# Hive_Server_-_Electron.net
KiCad netlist of a schematic drawn in EAGLE
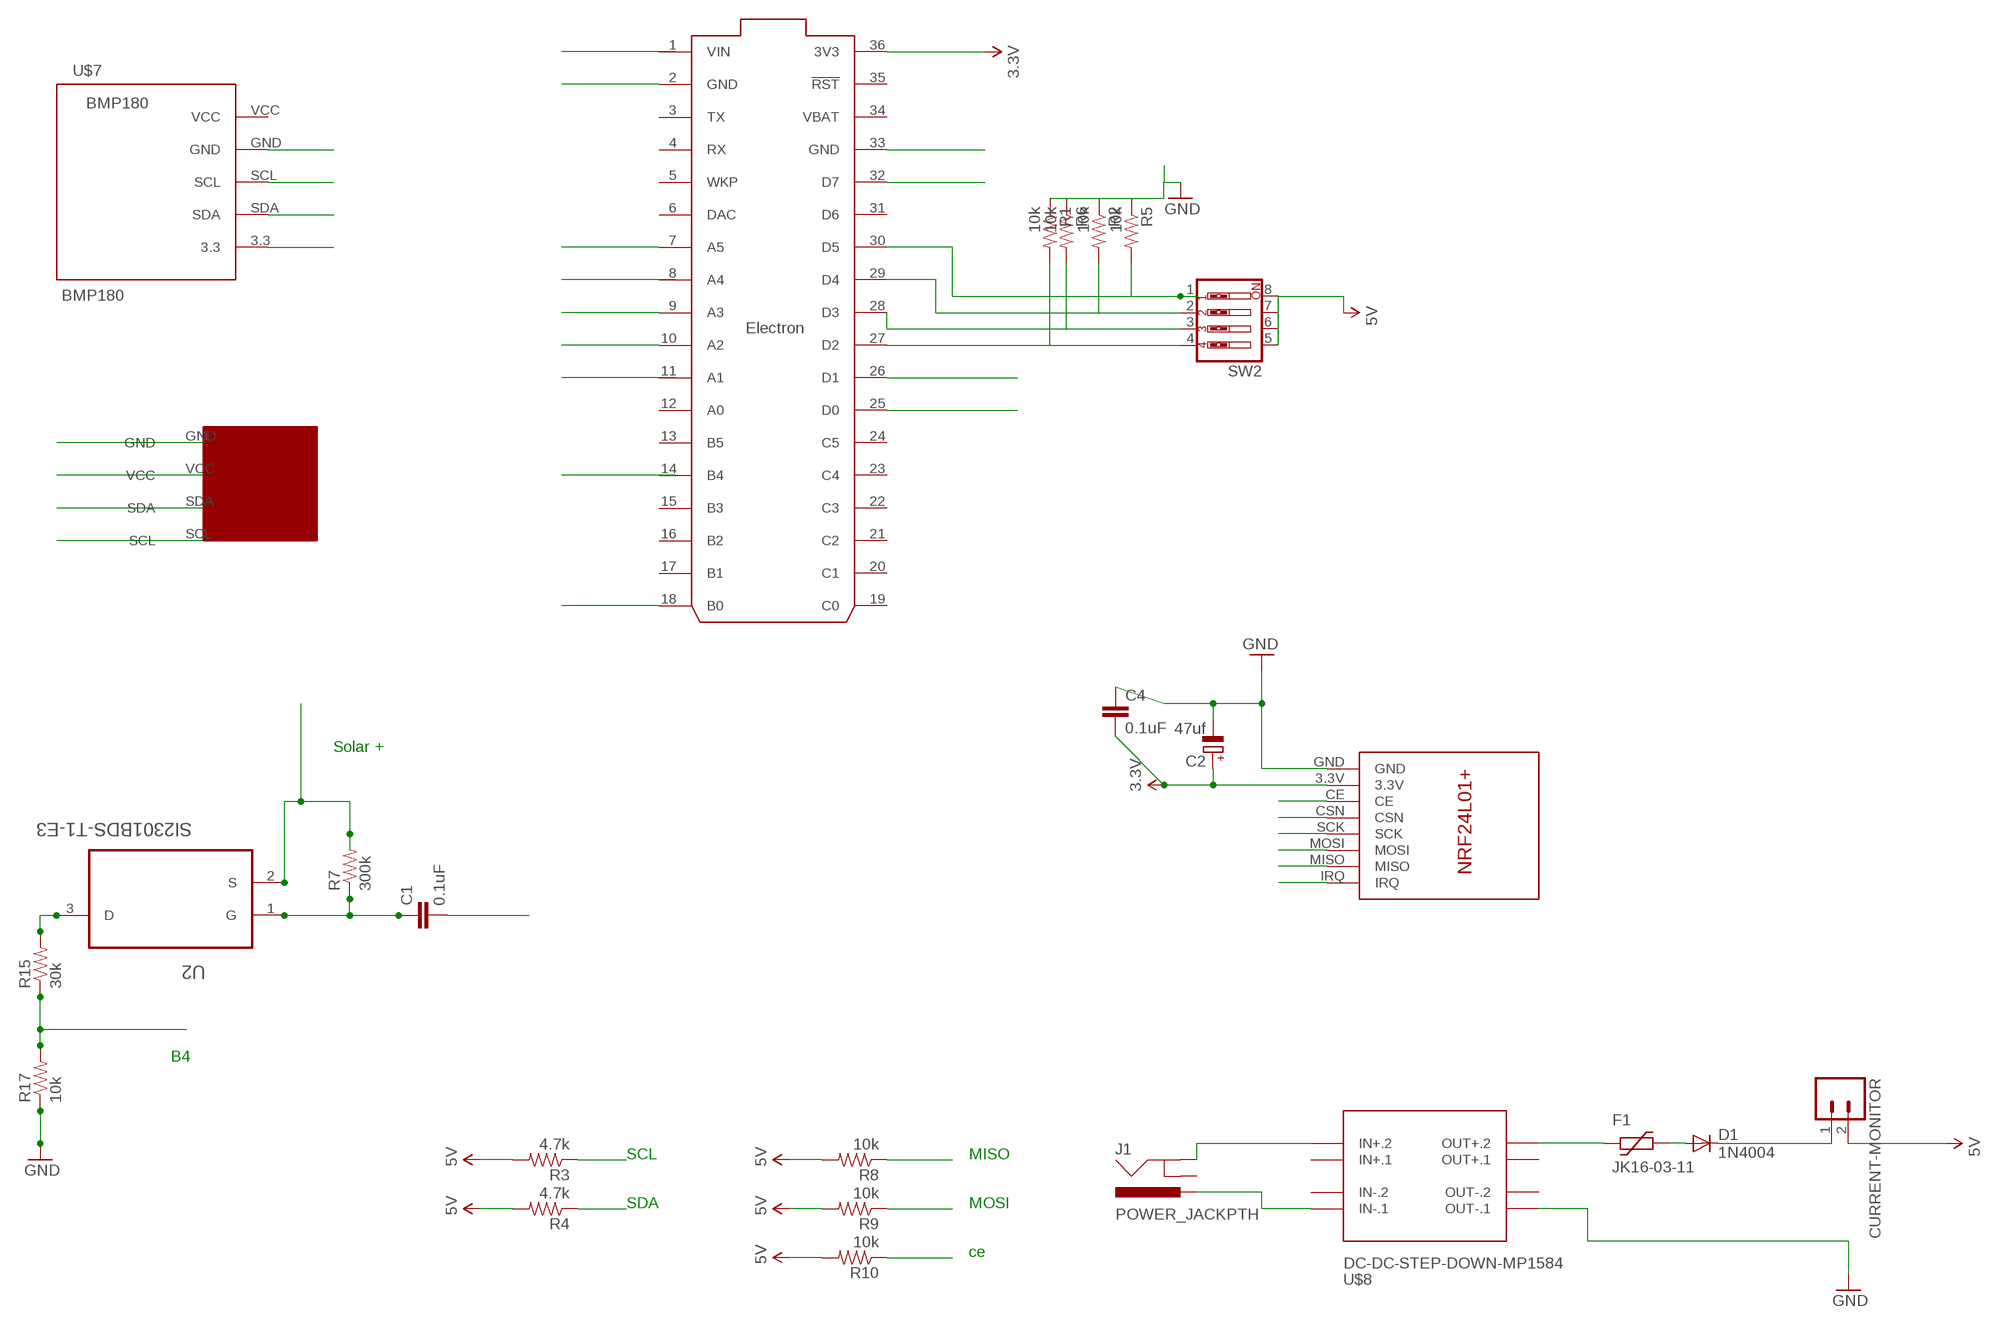
[diagram p0: schematic, sheet 1]

(export (version "E")
  (design (tool "Eeschema 10.0.6"))
  (components
    (comp (ref "C1")
      (value "0.1uF")
      (footprint "eagle-import:0805")
      (libsource (lib "eagle-import") (part "2.2UF-25V-+80/-20(0805)"))
    )
    (comp (ref "C2")
      (value "47uf")
      (footprint "eagle-import:E2,5-5")
      (libsource (lib "eagle-import") (part "CPOL-EUE2.5-5"))
    )
    (comp (ref "C4")
      (value "0.1uF")
      (footprint "eagle-import:0805")
      (libsource (lib "eagle-import") (part "2.2UF-25V-+80/-20(0805)"))
    )
    (comp (ref "CURRENT-MONITOR")
      (value "M02PTH")
      (footprint "eagle-import:1X02")
      (libsource (lib "eagle-import") (part "M02PTH"))
    )
    (comp (ref "D1")
      (value "1N4004")
      (footprint "eagle-import:DO41-10")
      (libsource (lib "eagle-import") (part "1N4004"))
    )
    (comp (ref "F1")
      (value "JK16-03-11")
      (footprint "eagle-import:JK16-03-11")
      (libsource (lib "eagle-import") (part "JK16-03-11"))
    )
    (comp (ref "J1")
      (value "POWER_JACKPTH")
      (footprint "eagle-import:POWER_JACK_PTH")
      (libsource (lib "eagle-import") (part "POWER_JACKPTH"))
    )
    (comp (ref "R1")
      (value "10k")
      (footprint "eagle-import:1206")
      (libsource (lib "eagle-import") (part "RESISTOR1206"))
    )
    (comp (ref "R2")
      (value "10k")
      (footprint "eagle-import:1206")
      (libsource (lib "eagle-import") (part "RESISTOR1206"))
    )
    (comp (ref "R3")
      (value "4.7k")
      (footprint "eagle-import:1206")
      (libsource (lib "eagle-import") (part "RESISTOR1206"))
    )
    (comp (ref "R4")
      (value "4.7k")
      (footprint "eagle-import:1206")
      (libsource (lib "eagle-import") (part "RESISTOR1206"))
    )
    (comp (ref "R5")
      (value "10k")
      (footprint "eagle-import:1206")
      (libsource (lib "eagle-import") (part "RESISTOR1206"))
    )
    (comp (ref "R6")
      (value "10k")
      (footprint "eagle-import:1206")
      (libsource (lib "eagle-import") (part "RESISTOR1206"))
    )
    (comp (ref "R7")
      (value "300k")
      (footprint "eagle-import:1_6W-RES")
      (libsource (lib "eagle-import") (part "SparkFun-Resistors_RESISTORPTH-1/6W"))
    )
    (comp (ref "R8")
      (value "10k")
      (footprint "eagle-import:1206")
      (libsource (lib "eagle-import") (part "RESISTOR1206"))
    )
    (comp (ref "R9")
      (value "10k")
      (footprint "eagle-import:1206")
      (libsource (lib "eagle-import") (part "RESISTOR1206"))
    )
    (comp (ref "R10")
      (value "10k")
      (footprint "eagle-import:1206")
      (libsource (lib "eagle-import") (part "RESISTOR1206"))
    )
    (comp (ref "R15")
      (value "30k")
      (footprint "eagle-import:1_6W-RES")
      (libsource (lib "eagle-import") (part "SparkFun-Resistors_RESISTORPTH-1/6W"))
    )
    (comp (ref "R17")
      (value "10k")
      (footprint "eagle-import:1_6W-RES")
      (libsource (lib "eagle-import") (part "SparkFun-Resistors_RESISTORPTH-1/6W"))
    )
    (comp (ref "SW2")
      (value "SW_DIP-4")
      (footprint "eagle-import:EDG-04")
      (libsource (lib "eagle-import") (part "SW_DIP-4"))
    )
    (comp (ref "U$1")
      (value "ELECTRON_WITH_HEADERS")
      (footprint "eagle-import:ELECTRON")
      (libsource (lib "eagle-import") (part "ELECTRON_WITH_HEADERS"))
    )
    (comp (ref "U$6")
      (value "NRF24L01")
      (footprint "eagle-import:NRF24L01")
      (libsource (lib "eagle-import") (part "NRF24L01"))
    )
    (comp (ref "U$7")
      (value "BMP180")
      (footprint "eagle-import:1X05")
      (libsource (lib "eagle-import") (part "BMP180BMP180"))
    )
    (comp (ref "U$8")
      (value "DC-DC-STEP-DOWN-MP1584")
      (footprint "eagle-import:DC-DC-STEP-DOWN-MP1584")
      (libsource (lib "eagle-import") (part "DC-DC-STEP-DOWN-MP1584"))
    )
    (comp (ref "U$13")
      (value "TJC8-4P")
      (footprint "eagle-import:TJC8-4P")
      (libsource (lib "eagle-import") (part "TJC8-4P"))
    )
    (comp (ref "U2")
      (value "SI2301BDS-T1-E3")
      (footprint "eagle-import:SOT95P237X112-3N")
      (libsource (lib "eagle-import") (part "SI2301BDS-T1-E3"))
    )
  )
  (nets
    (net (code "1") (name "/B4") (class "Default")
      (node (ref "R15") (pin "1") (pinfunction "1_1") (pintype "passive"))
      (node (ref "R17") (pin "2") (pinfunction "2_2") (pintype "passive"))
    )
    (net (code "2") (name "/CE_RADIO") (class "Default")
      (node (ref "R10") (pin "1") (pinfunction "1_1") (pintype "passive"))
      (node (ref "U$6") (pin "CE") (pinfunction "CE_CE") (pintype "bidirectional"))
    )
    (net (code "3") (name "/CSN") (class "Default")
      (node (ref "U$1") (pin "10") (pinfunction "A2_10") (pintype "bidirectional"))
      (node (ref "U$6") (pin "CSN") (pinfunction "CSN_CSN") (pintype "bidirectional"))
    )
    (net (code "4") (name "/D7") (class "Default")
      (node (ref "C1") (pin "2") (pinfunction "2_2") (pintype "passive"))
      (node (ref "U$1") (pin "32") (pinfunction "D7_32") (pintype "bidirectional"))
    )
    (net (code "5") (name "/IRQ") (class "Default")
      (node (ref "U$1") (pin "18") (pinfunction "B0_18") (pintype "bidirectional"))
      (node (ref "U$6") (pin "IRQ") (pinfunction "IRQ_IRQ") (pintype "bidirectional"))
    )
    (net (code "6") (name "/MISO") (class "Default")
      (node (ref "R8") (pin "1") (pinfunction "1_1") (pintype "passive"))
      (node (ref "U$6") (pin "MISO") (pinfunction "MISO_MISO") (pintype "bidirectional"))
    )
    (net (code "7") (name "/MOSI") (class "Default")
      (node (ref "R9") (pin "1") (pinfunction "1_1") (pintype "passive"))
      (node (ref "U$1") (pin "7") (pinfunction "A5_7") (pintype "bidirectional"))
      (node (ref "U$6") (pin "MOSI") (pinfunction "MOSI_MOSI") (pintype "bidirectional"))
    )
    (net (code "8") (name "/S+") (class "Default")
      (node (ref "J1") (pin "GND") (pinfunction "GND_GND") (pintype "bidirectional"))
      (node (ref "R7") (pin "2") (pinfunction "2_2") (pintype "passive"))
      (node (ref "U$8") (pin "IN+.2") (pinfunction "IN+.2_IN+.2") (pintype "bidirectional"))
      (node (ref "U2") (pin "2") (pinfunction "S_2") (pintype "passive"))
    )
    (net (code "9") (name "/SCK") (class "Default")
      (node (ref "U$1") (pin "9") (pinfunction "A3_9") (pintype "bidirectional"))
      (node (ref "U$6") (pin "SCK") (pinfunction "SCK_SCK") (pintype "bidirectional"))
    )
    (net (code "10") (name "/SCL") (class "Default")
      (node (ref "R3") (pin "1") (pinfunction "1_1") (pintype "passive"))
      (node (ref "U$1") (pin "26") (pinfunction "D1_26") (pintype "bidirectional"))
      (node (ref "U$13") (pin "SCL") (pinfunction "SCL_SCL") (pintype "bidirectional"))
      (node (ref "U$7") (pin "SCL") (pinfunction "SCL_SCL") (pintype "bidirectional"))
    )
    (net (code "11") (name "/SDA") (class "Default")
      (node (ref "R4") (pin "1") (pinfunction "1_1") (pintype "passive"))
      (node (ref "U$1") (pin "25") (pinfunction "D0_25") (pintype "bidirectional"))
      (node (ref "U$13") (pin "SDA") (pinfunction "SDA_SDA") (pintype "bidirectional"))
      (node (ref "U$7") (pin "SDA") (pinfunction "SDA_SDA") (pintype "bidirectional"))
    )
    (net (code "12") (name "/VBAT") (class "Default")
      (node (ref "U$1") (pin "34") (pinfunction "VBAT_34") (pintype "power_in"))
    )
    (net (code "13") (name "/VIN") (class "Default")
      (node (ref "U$1") (pin "1") (pinfunction "VIN_1") (pintype "power_in"))
    )
    (net (code "14") (name "3.3V") (class "Default")
      (node (ref "C2") (pin "+") (pinfunction "+_+") (pintype "passive"))
      (node (ref "C4") (pin "2") (pinfunction "2_2") (pintype "passive"))
      (node (ref "U$1") (pin "36") (pinfunction "3V3_36") (pintype "power_in"))
      (node (ref "U$6") (pin "3.3V") (pinfunction "3.3V_3.3V") (pintype "bidirectional"))
      (node (ref "U$7") (pin "3.3") (pinfunction "3.3_3.3") (pintype "bidirectional"))
    )
    (net (code "15") (name "5V") (class "Default")
      (node (ref "CURRENT-MONITOR") (pin "2") (pinfunction "2_2") (pintype "passive"))
      (node (ref "R10") (pin "2") (pinfunction "2_2") (pintype "passive"))
      (node (ref "R3") (pin "2") (pinfunction "2_2") (pintype "passive"))
      (node (ref "R4") (pin "2") (pinfunction "2_2") (pintype "passive"))
      (node (ref "R8") (pin "2") (pinfunction "2_2") (pintype "passive"))
      (node (ref "R9") (pin "2") (pinfunction "2_2") (pintype "passive"))
      (node (ref "SW2") (pin "5") (pinfunction "5_5") (pintype "passive"))
      (node (ref "SW2") (pin "6") (pinfunction "6_6") (pintype "passive"))
      (node (ref "SW2") (pin "7") (pinfunction "7_7") (pintype "passive"))
      (node (ref "SW2") (pin "8") (pinfunction "8_8") (pintype "passive"))
      (node (ref "U$13") (pin "VCC") (pinfunction "VCC_VCC") (pintype "bidirectional"))
    )
    (net (code "16") (name "GND") (class "Default")
      (node (ref "C2") (pin "-") (pinfunction "-_-") (pintype "passive"))
      (node (ref "C4") (pin "1") (pinfunction "1_1") (pintype "passive"))
      (node (ref "R1") (pin "1") (pinfunction "1_1") (pintype "passive"))
      (node (ref "R17") (pin "1") (pinfunction "1_1") (pintype "passive"))
      (node (ref "R2") (pin "1") (pinfunction "1_1") (pintype "passive"))
      (node (ref "R5") (pin "1") (pinfunction "1_1") (pintype "passive"))
      (node (ref "R6") (pin "1") (pinfunction "1_1") (pintype "passive"))
      (node (ref "U$1") (pin "2") (pinfunction "GND_2") (pintype "power_in"))
      (node (ref "U$1") (pin "33") (pinfunction "GND_33") (pintype "power_in"))
      (node (ref "U$13") (pin "GND") (pinfunction "GND_GND") (pintype "bidirectional"))
      (node (ref "U$6") (pin "GND") (pinfunction "GND_GND") (pintype "bidirectional"))
      (node (ref "U$7") (pin "GND") (pinfunction "GND_GND") (pintype "bidirectional"))
      (node (ref "U$8") (pin "OUT-.1") (pinfunction "OUT-.1_OUT-.1") (pintype "bidirectional"))
    )
    (net (code "17") (name "Net-(CURRENT-MONITOR-Pad1)") (class "Default")
      (node (ref "CURRENT-MONITOR") (pin "1") (pinfunction "1_1") (pintype "passive"))
      (node (ref "D1") (pin "C") (pinfunction "C_C") (pintype "passive"))
    )
    (net (code "18") (name "Net-(F1-1)") (class "Default")
      (node (ref "F1") (pin "P$1") (pinfunction "1_P$1") (pintype "passive"))
      (node (ref "U$8") (pin "OUT+.2") (pinfunction "OUT+.2_OUT+.2") (pintype "bidirectional"))
    )
    (net (code "19") (name "Net-(F1-2)") (class "Default")
      (node (ref "D1") (pin "A") (pinfunction "A_A") (pintype "passive"))
      (node (ref "F1") (pin "P$2") (pinfunction "2_P$2") (pintype "passive"))
    )
    (net (code "20") (name "Net-(J1-PadPWR)") (class "Default")
      (node (ref "J1") (pin "PWR") (pinfunction "PWR_PWR") (pintype "bidirectional"))
      (node (ref "U$8") (pin "IN-.1") (pinfunction "IN-.1_IN-.1") (pintype "bidirectional"))
    )
    (net (code "21") (name "Net-(U$1-D2)") (class "Default")
      (node (ref "R1") (pin "2") (pinfunction "2_2") (pintype "passive"))
      (node (ref "SW2") (pin "4") (pinfunction "4_4") (pintype "passive"))
      (node (ref "U$1") (pin "27") (pinfunction "D2_27") (pintype "bidirectional"))
    )
    (net (code "22") (name "Net-(U$1-D3)") (class "Default")
      (node (ref "R6") (pin "2") (pinfunction "2_2") (pintype "passive"))
      (node (ref "SW2") (pin "3") (pinfunction "3_3") (pintype "passive"))
      (node (ref "U$1") (pin "28") (pinfunction "D3_28") (pintype "bidirectional"))
    )
    (net (code "23") (name "Net-(U$1-D4)") (class "Default")
      (node (ref "R2") (pin "2") (pinfunction "2_2") (pintype "passive"))
      (node (ref "SW2") (pin "2") (pinfunction "2_2") (pintype "passive"))
      (node (ref "U$1") (pin "29") (pinfunction "D4_29") (pintype "bidirectional"))
    )
    (net (code "24") (name "Net-(U$1-D5)") (class "Default")
      (node (ref "R5") (pin "2") (pinfunction "2_2") (pintype "passive"))
      (node (ref "SW2") (pin "1") (pinfunction "1_1") (pintype "passive"))
      (node (ref "U$1") (pin "30") (pinfunction "D5_30") (pintype "bidirectional"))
    )
    (net (code "25") (name "Net-(U2-D)") (class "Default")
      (node (ref "R15") (pin "2") (pinfunction "2_2") (pintype "passive"))
      (node (ref "U2") (pin "3") (pinfunction "D_3") (pintype "passive"))
    )
    (net (code "26") (name "Net-(U2-G)") (class "Default")
      (node (ref "C1") (pin "1") (pinfunction "1_1") (pintype "passive"))
      (node (ref "R7") (pin "1") (pinfunction "1_1") (pintype "passive"))
      (node (ref "U2") (pin "1") (pinfunction "G_1") (pintype "passive"))
    )
    (net (code "27") (name "unconnected-(J1-PadGNDBREAK)") (class "Default")
      (node (ref "J1") (pin "GNDBREAK") (pinfunction "GNDBREAK_GNDBREAK") (pintype "bidirectional"))
    )
    (net (code "28") (name "unconnected-(U$1-A0-Pad12)") (class "Default")
      (node (ref "U$1") (pin "12") (pinfunction "A0_12") (pintype "bidirectional"))
    )
    (net (code "29") (name "unconnected-(U$1-A1-Pad11)") (class "Default")
      (node (ref "U$1") (pin "11") (pinfunction "A1_11") (pintype "bidirectional"))
    )
    (net (code "30") (name "unconnected-(U$1-A4-Pad8)") (class "Default")
      (node (ref "U$1") (pin "8") (pinfunction "A4_8") (pintype "bidirectional"))
    )
    (net (code "31") (name "unconnected-(U$1-B1-Pad17)") (class "Default")
      (node (ref "U$1") (pin "17") (pinfunction "B1_17") (pintype "bidirectional"))
    )
    (net (code "32") (name "unconnected-(U$1-B2-Pad16)") (class "Default")
      (node (ref "U$1") (pin "16") (pinfunction "B2_16") (pintype "bidirectional"))
    )
    (net (code "33") (name "unconnected-(U$1-B3-Pad15)") (class "Default")
      (node (ref "U$1") (pin "15") (pinfunction "B3_15") (pintype "bidirectional"))
    )
    (net (code "34") (name "unconnected-(U$1-B4-Pad14)") (class "Default")
      (node (ref "U$1") (pin "14") (pinfunction "B4_14") (pintype "bidirectional"))
    )
    (net (code "35") (name "unconnected-(U$1-B5-Pad13)") (class "Default")
      (node (ref "U$1") (pin "13") (pinfunction "B5_13") (pintype "bidirectional"))
    )
    (net (code "36") (name "unconnected-(U$1-C0-Pad19)") (class "Default")
      (node (ref "U$1") (pin "19") (pinfunction "C0_19") (pintype "bidirectional"))
    )
    (net (code "37") (name "unconnected-(U$1-C1-Pad20)") (class "Default")
      (node (ref "U$1") (pin "20") (pinfunction "C1_20") (pintype "bidirectional"))
    )
    (net (code "38") (name "unconnected-(U$1-C2-Pad21)") (class "Default")
      (node (ref "U$1") (pin "21") (pinfunction "C2_21") (pintype "bidirectional"))
    )
    (net (code "39") (name "unconnected-(U$1-C3-Pad22)") (class "Default")
      (node (ref "U$1") (pin "22") (pinfunction "C3_22") (pintype "bidirectional"))
    )
    (net (code "40") (name "unconnected-(U$1-C4-Pad23)") (class "Default")
      (node (ref "U$1") (pin "23") (pinfunction "C4_23") (pintype "bidirectional"))
    )
    (net (code "41") (name "unconnected-(U$1-C5-Pad24)") (class "Default")
      (node (ref "U$1") (pin "24") (pinfunction "C5_24") (pintype "bidirectional"))
    )
    (net (code "42") (name "unconnected-(U$1-D6-Pad31)") (class "Default")
      (node (ref "U$1") (pin "31") (pinfunction "D6_31") (pintype "bidirectional"))
    )
    (net (code "43") (name "unconnected-(U$1-DAC-Pad6)") (class "Default")
      (node (ref "U$1") (pin "6") (pinfunction "DAC_6") (pintype "bidirectional"))
    )
    (net (code "44") (name "unconnected-(U$1-RX-Pad4)") (class "Default")
      (node (ref "U$1") (pin "4") (pinfunction "RX_4") (pintype "bidirectional"))
    )
    (net (code "45") (name "unconnected-(U$1-TX-Pad3)") (class "Default")
      (node (ref "U$1") (pin "3") (pinfunction "TX_3") (pintype "bidirectional"))
    )
    (net (code "46") (name "unconnected-(U$1-WKP-Pad5)") (class "Default")
      (node (ref "U$1") (pin "5") (pinfunction "WKP_5") (pintype "bidirectional"))
    )
    (net (code "47") (name "unconnected-(U$1-~{RST}-Pad35)") (class "Default")
      (node (ref "U$1") (pin "35") (pinfunction "~{RST}_35") (pintype "bidirectional"))
    )
    (net (code "48") (name "unconnected-(U$7-PadVCC)") (class "Default")
      (node (ref "U$7") (pin "VCC") (pinfunction "VCC_VCC") (pintype "bidirectional"))
    )
    (net (code "49") (name "unconnected-(U$8-PadIN+.1)") (class "Default")
      (node (ref "U$8") (pin "IN+.1") (pinfunction "IN+.1_IN+.1") (pintype "bidirectional"))
    )
    (net (code "50") (name "unconnected-(U$8-PadIN-.2)") (class "Default")
      (node (ref "U$8") (pin "IN-.2") (pinfunction "IN-.2_IN-.2") (pintype "bidirectional"))
    )
    (net (code "51") (name "unconnected-(U$8-PadOUT+.1)") (class "Default")
      (node (ref "U$8") (pin "OUT+.1") (pinfunction "OUT+.1_OUT+.1") (pintype "bidirectional"))
    )
    (net (code "52") (name "unconnected-(U$8-PadOUT-.2)") (class "Default")
      (node (ref "U$8") (pin "OUT-.2") (pinfunction "OUT-.2_OUT-.2") (pintype "bidirectional"))
    )
  )
)
